# LED_7_Thanh.net
KiCad netlist of a schematic drawn in Altium Designer
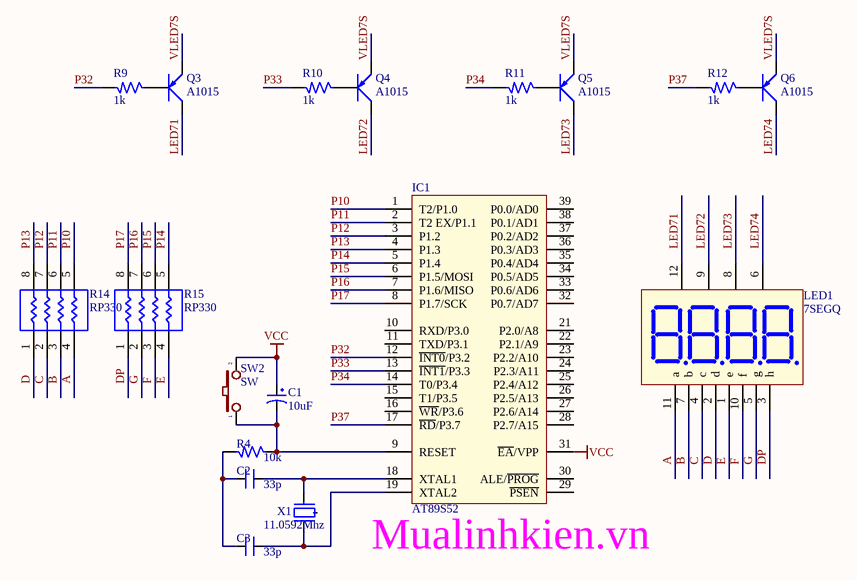
[diagram p0: LED 7 Thanh.SchDoc]

(export (version "E")
  (design (tool "Eeschema 10.0.6"))
  (components
    (comp (ref "C1")
      (value "10uF")
      (footprint "CP1/2")
      (description "Cap P  0,1uF < 22uF , 16 - 50V")
      (libsource (lib "syhaunguyen") (part "CP1"))
    )
    (comp (ref "C2")
      (value "33p")
      (footprint "SM-0805")
      (description "Cap np  1pF - 472pF")
      (libsource (lib "syhaunguyen") (part "CN1"))
    )
    (comp (ref "C3")
      (value "33p")
      (footprint "SM-0805")
      (description "Cap np  1pF - 472pF")
      (libsource (lib "syhaunguyen") (part "CN1"))
    )
    (comp (ref "IC1")
      (value "AT89S52")
      (footprint "ZIP40")
      (description "AT89S52, 8k Byte Flash Memory , 40 Pin")
      (libsource (lib "syhaunguyen") (part "AT89S52"))
    )
    (comp (ref "LED1")
      (value "7SEGQ")
      (footprint "7SEGQ-n")
      (description "Four 7 Seg Dipslay")
      (libsource (lib "syhaunguyen") (part "LED7Q"))
    )
    (comp (ref "Q3")
      (value "A1015")
      (footprint "SOT23B")
      (description "PNP 600mW, ECB")
      (libsource (lib "syhaunguyen") (part "A1015"))
    )
    (comp (ref "Q4")
      (value "A1015")
      (footprint "SOT23B")
      (description "PNP 600mW, ECB")
      (libsource (lib "syhaunguyen") (part "A1015"))
    )
    (comp (ref "Q5")
      (value "A1015")
      (footprint "SOT23B")
      (description "PNP 600mW, ECB")
      (libsource (lib "syhaunguyen") (part "A1015"))
    )
    (comp (ref "Q6")
      (value "A1015")
      (footprint "SOT23B")
      (description "PNP 600mW, ECB")
      (libsource (lib "syhaunguyen") (part "A1015"))
    )
    (comp (ref "R4")
      (value "10k")
      (footprint "SM-RES-0805")
      (description "Resistor 1/4W")
      (libsource (lib "syhaunguyen") (part "R"))
    )
    (comp (ref "R9")
      (value "1k")
      (footprint "SM-RES-0805")
      (description "Resistor 1/4W")
      (libsource (lib "syhaunguyen") (part "R"))
    )
    (comp (ref "R10")
      (value "1k")
      (footprint "SM-RES-0805")
      (description "Resistor 1/4W")
      (libsource (lib "syhaunguyen") (part "R"))
    )
    (comp (ref "R11")
      (value "1k")
      (footprint "SM-RES-0805")
      (description "Resistor 1/4W")
      (libsource (lib "syhaunguyen") (part "R"))
    )
    (comp (ref "R12")
      (value "1k")
      (footprint "SM-RES-0805")
      (description "Resistor 1/4W")
      (libsource (lib "syhaunguyen") (part "R"))
    )
    (comp (ref "R14")
      (value "RP330")
      (footprint "RESCAXS50P160X320X70-8N")
      (libsource (lib "Sonbui") (part "ResPack"))
    )
    (comp (ref "R15")
      (value "RP330")
      (footprint "RESCAXS50P160X320X70-8N")
      (libsource (lib "Sonbui") (part "ResPack"))
    )
    (comp (ref "SW2")
      (value "SW")
      (footprint "SW-SMD")
      (description "Switch button 2 pin")
      (libsource (lib "syhaunguyen") (part "SW2"))
    )
    (comp (ref "X1")
      (value "11.0592Mhz")
      (footprint "XT3")
      (description "Crystal For all Crystal 2pin.")
      (libsource (lib "syhaunguyen") (part "XT3"))
    )
  )
  (nets
    (net (code "1") (name "/A") (class "Default")
      (node (ref "LED1") (pin "11") (pinfunction "a_11") (pintype "passive"))
      (node (ref "R14") (pin "4") (pinfunction "4_4") (pintype "passive"))
    )
    (net (code "2") (name "/B") (class "Default")
      (node (ref "LED1") (pin "7") (pinfunction "b_7") (pintype "passive"))
      (node (ref "R14") (pin "3") (pinfunction "3_3") (pintype "passive"))
    )
    (net (code "3") (name "/C") (class "Default")
      (node (ref "LED1") (pin "4") (pinfunction "c_4") (pintype "passive"))
      (node (ref "R14") (pin "2") (pinfunction "2_2") (pintype "passive"))
    )
    (net (code "4") (name "/D") (class "Default")
      (node (ref "LED1") (pin "2") (pinfunction "d_2") (pintype "passive"))
      (node (ref "R14") (pin "1") (pinfunction "1_1") (pintype "passive"))
    )
    (net (code "5") (name "/DP") (class "Default")
      (node (ref "LED1") (pin "3") (pinfunction "h_3") (pintype "passive"))
      (node (ref "R15") (pin "1") (pinfunction "1_1") (pintype "passive"))
    )
    (net (code "6") (name "/E") (class "Default")
      (node (ref "LED1") (pin "1") (pinfunction "e_1") (pintype "passive"))
      (node (ref "R15") (pin "4") (pinfunction "4_4") (pintype "passive"))
    )
    (net (code "7") (name "/F") (class "Default")
      (node (ref "LED1") (pin "10") (pinfunction "f_10") (pintype "passive"))
      (node (ref "R15") (pin "3") (pinfunction "3_3") (pintype "passive"))
    )
    (net (code "8") (name "/G") (class "Default")
      (node (ref "LED1") (pin "5") (pinfunction "g_5") (pintype "passive"))
      (node (ref "R15") (pin "2") (pinfunction "2_2") (pintype "passive"))
    )
    (net (code "9") (name "/LED71") (class "Default")
      (node (ref "LED1") (pin "12") (pinfunction "V1_12") (pintype "passive"))
      (node (ref "Q3") (pin "2") (pinfunction "C_2") (pintype "passive"))
    )
    (net (code "10") (name "/LED72") (class "Default")
      (node (ref "LED1") (pin "9") (pinfunction "V2_9") (pintype "passive"))
      (node (ref "Q4") (pin "2") (pinfunction "C_2") (pintype "passive"))
    )
    (net (code "11") (name "/LED73") (class "Default")
      (node (ref "LED1") (pin "8") (pinfunction "V3_8") (pintype "passive"))
      (node (ref "Q5") (pin "2") (pinfunction "C_2") (pintype "passive"))
    )
    (net (code "12") (name "/LED74") (class "Default")
      (node (ref "LED1") (pin "6") (pinfunction "V4_6") (pintype "passive"))
      (node (ref "Q6") (pin "2") (pinfunction "C_2") (pintype "passive"))
    )
    (net (code "14") (name "/P10") (class "Default")
      (node (ref "IC1") (pin "1") (pinfunction "T2/P1.0_1") (pintype "passive"))
      (node (ref "R14") (pin "5") (pinfunction "5_5") (pintype "passive"))
    )
    (net (code "15") (name "/P11") (class "Default")
      (node (ref "IC1") (pin "2") (pinfunction "T2_EX/P1.1_2") (pintype "passive"))
      (node (ref "R14") (pin "6") (pinfunction "6_6") (pintype "passive"))
    )
    (net (code "16") (name "/P12") (class "Default")
      (node (ref "IC1") (pin "3") (pinfunction "P1.2_3") (pintype "passive"))
      (node (ref "R14") (pin "7") (pinfunction "7_7") (pintype "passive"))
    )
    (net (code "17") (name "/P13") (class "Default")
      (node (ref "IC1") (pin "4") (pinfunction "P1.3_4") (pintype "passive"))
      (node (ref "R14") (pin "8") (pinfunction "8_8") (pintype "passive"))
    )
    (net (code "18") (name "/P14") (class "Default")
      (node (ref "IC1") (pin "5") (pinfunction "P1.4_5") (pintype "passive"))
      (node (ref "R15") (pin "5") (pinfunction "5_5") (pintype "passive"))
    )
    (net (code "19") (name "/P15") (class "Default")
      (node (ref "IC1") (pin "6") (pinfunction "P1.5/MOSI_6") (pintype "passive"))
      (node (ref "R15") (pin "6") (pinfunction "6_6") (pintype "passive"))
    )
    (net (code "20") (name "/P16") (class "Default")
      (node (ref "IC1") (pin "7") (pinfunction "P1.6/MISO_7") (pintype "passive"))
      (node (ref "R15") (pin "7") (pinfunction "7_7") (pintype "passive"))
    )
    (net (code "21") (name "/P17") (class "Default")
      (node (ref "IC1") (pin "8") (pinfunction "P1.7/SCK_8") (pintype "passive"))
      (node (ref "R15") (pin "8") (pinfunction "8_8") (pintype "passive"))
    )
    (net (code "22") (name "/P32") (class "Default")
      (node (ref "IC1") (pin "12") (pinfunction "~{INT0}/P3.2_12") (pintype "passive"))
      (node (ref "R9") (pin "2") (pinfunction "2_2") (pintype "passive"))
    )
    (net (code "23") (name "/P33") (class "Default")
      (node (ref "IC1") (pin "13") (pinfunction "~{INT1}/P3.3_13") (pintype "passive"))
      (node (ref "R10") (pin "2") (pinfunction "2_2") (pintype "passive"))
    )
    (net (code "24") (name "/P34") (class "Default")
      (node (ref "IC1") (pin "14") (pinfunction "T0/P3.4_14") (pintype "passive"))
      (node (ref "R11") (pin "2") (pinfunction "2_2") (pintype "passive"))
    )
    (net (code "25") (name "/P37") (class "Default")
      (node (ref "IC1") (pin "17") (pinfunction "~{RD}/P3.7_17") (pintype "passive"))
      (node (ref "R12") (pin "2") (pinfunction "2_2") (pintype "passive"))
    )
    (net (code "26") (name "/VLED7S") (class "Default")
      (node (ref "Q3") (pin "1") (pinfunction "E_1") (pintype "passive"))
      (node (ref "Q4") (pin "1") (pinfunction "E_1") (pintype "passive"))
      (node (ref "Q5") (pin "1") (pinfunction "E_1") (pintype "passive"))
      (node (ref "Q6") (pin "1") (pinfunction "E_1") (pintype "passive"))
    )
    (net (code "27") (name "GND") (class "Default")
      (node (ref "IC1") (pin "20") (pinfunction "GND_20") (pintype "power_in"))
    )
    (net (code "28") (name "Net-(C2-Pad1)") (class "Default")
      (node (ref "C2") (pin "1") (pinfunction "1_1") (pintype "passive"))
      (node (ref "C3") (pin "1") (pinfunction "1_1") (pintype "passive"))
      (node (ref "R4") (pin "2") (pinfunction "2_2") (pintype "passive"))
    )
    (net (code "29") (name "Net-(IC1-RESET)") (class "Default")
      (node (ref "C1") (pin "2") (pinfunction "2_2") (pintype "passive"))
      (node (ref "IC1") (pin "9") (pinfunction "RESET_9") (pintype "passive"))
      (node (ref "R4") (pin "1") (pinfunction "1_1") (pintype "passive"))
      (node (ref "SW2") (pin "1") (pinfunction "1_1") (pintype "passive"))
    )
    (net (code "30") (name "Net-(IC1-XTAL1)") (class "Default")
      (node (ref "C2") (pin "2") (pinfunction "2_2") (pintype "passive"))
      (node (ref "IC1") (pin "18") (pinfunction "XTAL1_18") (pintype "passive"))
      (node (ref "X1") (pin "2") (pinfunction "2_2") (pintype "passive"))
    )
    (net (code "31") (name "Net-(IC1-XTAL2)") (class "Default")
      (node (ref "C3") (pin "2") (pinfunction "2_2") (pintype "passive"))
      (node (ref "IC1") (pin "19") (pinfunction "XTAL2_19") (pintype "passive"))
      (node (ref "X1") (pin "1") (pinfunction "1_1") (pintype "passive"))
    )
    (net (code "32") (name "Net-(Q3-B)") (class "Default")
      (node (ref "Q3") (pin "3") (pinfunction "B_3") (pintype "passive"))
      (node (ref "R9") (pin "1") (pinfunction "1_1") (pintype "passive"))
    )
    (net (code "33") (name "Net-(Q4-B)") (class "Default")
      (node (ref "Q4") (pin "3") (pinfunction "B_3") (pintype "passive"))
      (node (ref "R10") (pin "1") (pinfunction "1_1") (pintype "passive"))
    )
    (net (code "34") (name "Net-(Q5-B)") (class "Default")
      (node (ref "Q5") (pin "3") (pinfunction "B_3") (pintype "passive"))
      (node (ref "R11") (pin "1") (pinfunction "1_1") (pintype "passive"))
    )
    (net (code "35") (name "Net-(Q6-B)") (class "Default")
      (node (ref "Q6") (pin "3") (pinfunction "B_3") (pintype "passive"))
      (node (ref "R12") (pin "1") (pinfunction "1_1") (pintype "passive"))
    )
    (net (code "36") (name "VCC") (class "Default")
      (node (ref "C1") (pin "1") (pinfunction "1_1") (pintype "passive"))
      (node (ref "IC1") (pin "31") (pinfunction "~{EA}/VPP_31") (pintype "passive"))
      (node (ref "IC1") (pin "40") (pinfunction "VCC_40") (pintype "power_in"))
      (node (ref "SW2") (pin "2") (pinfunction "2_2") (pintype "passive"))
    )
    (net (code "37") (name "unconnected-(IC1-ALE{slash}~{PROG}-Pad30)") (class "Default")
      (node (ref "IC1") (pin "30") (pinfunction "ALE/~{PROG}_30") (pintype "passive"))
    )
    (net (code "38") (name "unconnected-(IC1-P0.0{slash}AD0-Pad39)") (class "Default")
      (node (ref "IC1") (pin "39") (pinfunction "P0.0/AD0_39") (pintype "passive"))
    )
    (net (code "39") (name "unconnected-(IC1-P0.1{slash}AD1-Pad38)") (class "Default")
      (node (ref "IC1") (pin "38") (pinfunction "P0.1/AD1_38") (pintype "passive"))
    )
    (net (code "40") (name "unconnected-(IC1-P0.2{slash}AD2-Pad37)") (class "Default")
      (node (ref "IC1") (pin "37") (pinfunction "P0.2/AD2_37") (pintype "passive"))
    )
    (net (code "41") (name "unconnected-(IC1-P0.3{slash}AD3-Pad36)") (class "Default")
      (node (ref "IC1") (pin "36") (pinfunction "P0.3/AD3_36") (pintype "passive"))
    )
    (net (code "42") (name "unconnected-(IC1-P0.4{slash}AD4-Pad35)") (class "Default")
      (node (ref "IC1") (pin "35") (pinfunction "P0.4/AD4_35") (pintype "passive"))
    )
    (net (code "43") (name "unconnected-(IC1-P0.5{slash}AD5-Pad34)") (class "Default")
      (node (ref "IC1") (pin "34") (pinfunction "P0.5/AD5_34") (pintype "passive"))
    )
    (net (code "44") (name "unconnected-(IC1-P0.6{slash}AD6-Pad33)") (class "Default")
      (node (ref "IC1") (pin "33") (pinfunction "P0.6/AD6_33") (pintype "passive"))
    )
    (net (code "45") (name "unconnected-(IC1-P0.7{slash}AD7-Pad32)") (class "Default")
      (node (ref "IC1") (pin "32") (pinfunction "P0.7/AD7_32") (pintype "passive"))
    )
    (net (code "46") (name "unconnected-(IC1-P2.0{slash}A8-Pad21)") (class "Default")
      (node (ref "IC1") (pin "21") (pinfunction "P2.0/A8_21") (pintype "passive"))
    )
    (net (code "47") (name "unconnected-(IC1-P2.1{slash}A9-Pad22)") (class "Default")
      (node (ref "IC1") (pin "22") (pinfunction "P2.1/A9_22") (pintype "passive"))
    )
    (net (code "48") (name "unconnected-(IC1-P2.2{slash}A10-Pad23)") (class "Default")
      (node (ref "IC1") (pin "23") (pinfunction "P2.2/A10_23") (pintype "passive"))
    )
    (net (code "49") (name "unconnected-(IC1-P2.3{slash}A11-Pad24)") (class "Default")
      (node (ref "IC1") (pin "24") (pinfunction "P2.3/A11_24") (pintype "passive"))
    )
    (net (code "50") (name "unconnected-(IC1-P2.4{slash}A12-Pad25)") (class "Default")
      (node (ref "IC1") (pin "25") (pinfunction "P2.4/A12_25") (pintype "passive"))
    )
    (net (code "51") (name "unconnected-(IC1-P2.5{slash}A13-Pad26)") (class "Default")
      (node (ref "IC1") (pin "26") (pinfunction "P2.5/A13_26") (pintype "passive"))
    )
    (net (code "52") (name "unconnected-(IC1-P2.6{slash}A14-Pad27)") (class "Default")
      (node (ref "IC1") (pin "27") (pinfunction "P2.6/A14_27") (pintype "passive"))
    )
    (net (code "53") (name "unconnected-(IC1-P2.7{slash}A15-Pad28)") (class "Default")
      (node (ref "IC1") (pin "28") (pinfunction "P2.7/A15_28") (pintype "passive"))
    )
    (net (code "54") (name "unconnected-(IC1-RXD{slash}P3.0-Pad10)") (class "Default")
      (node (ref "IC1") (pin "10") (pinfunction "RXD/P3.0_10") (pintype "passive"))
    )
    (net (code "55") (name "unconnected-(IC1-T1{slash}P3.5-Pad15)") (class "Default")
      (node (ref "IC1") (pin "15") (pinfunction "T1/P3.5_15") (pintype "passive"))
    )
    (net (code "56") (name "unconnected-(IC1-TXD{slash}P3.1-Pad11)") (class "Default")
      (node (ref "IC1") (pin "11") (pinfunction "TXD/P3.1_11") (pintype "passive"))
    )
    (net (code "57") (name "unconnected-(IC1-~{PSEN}-Pad29)") (class "Default")
      (node (ref "IC1") (pin "29") (pinfunction "~{PSEN}_29") (pintype "passive"))
    )
    (net (code "58") (name "unconnected-(IC1-~{WR}{slash}P3.6-Pad16)") (class "Default")
      (node (ref "IC1") (pin "16") (pinfunction "~{WR}/P3.6_16") (pintype "passive"))
    )
    (net (code "59") (name "unconnected-(X1-Pad3)") (class "Default")
      (node (ref "X1") (pin "3") (pinfunction "3_3") (pintype "passive"))
    )
  )
)
